# Schematic_Sensing_Module.net
KiCad netlist of a schematic drawn in EAGLE
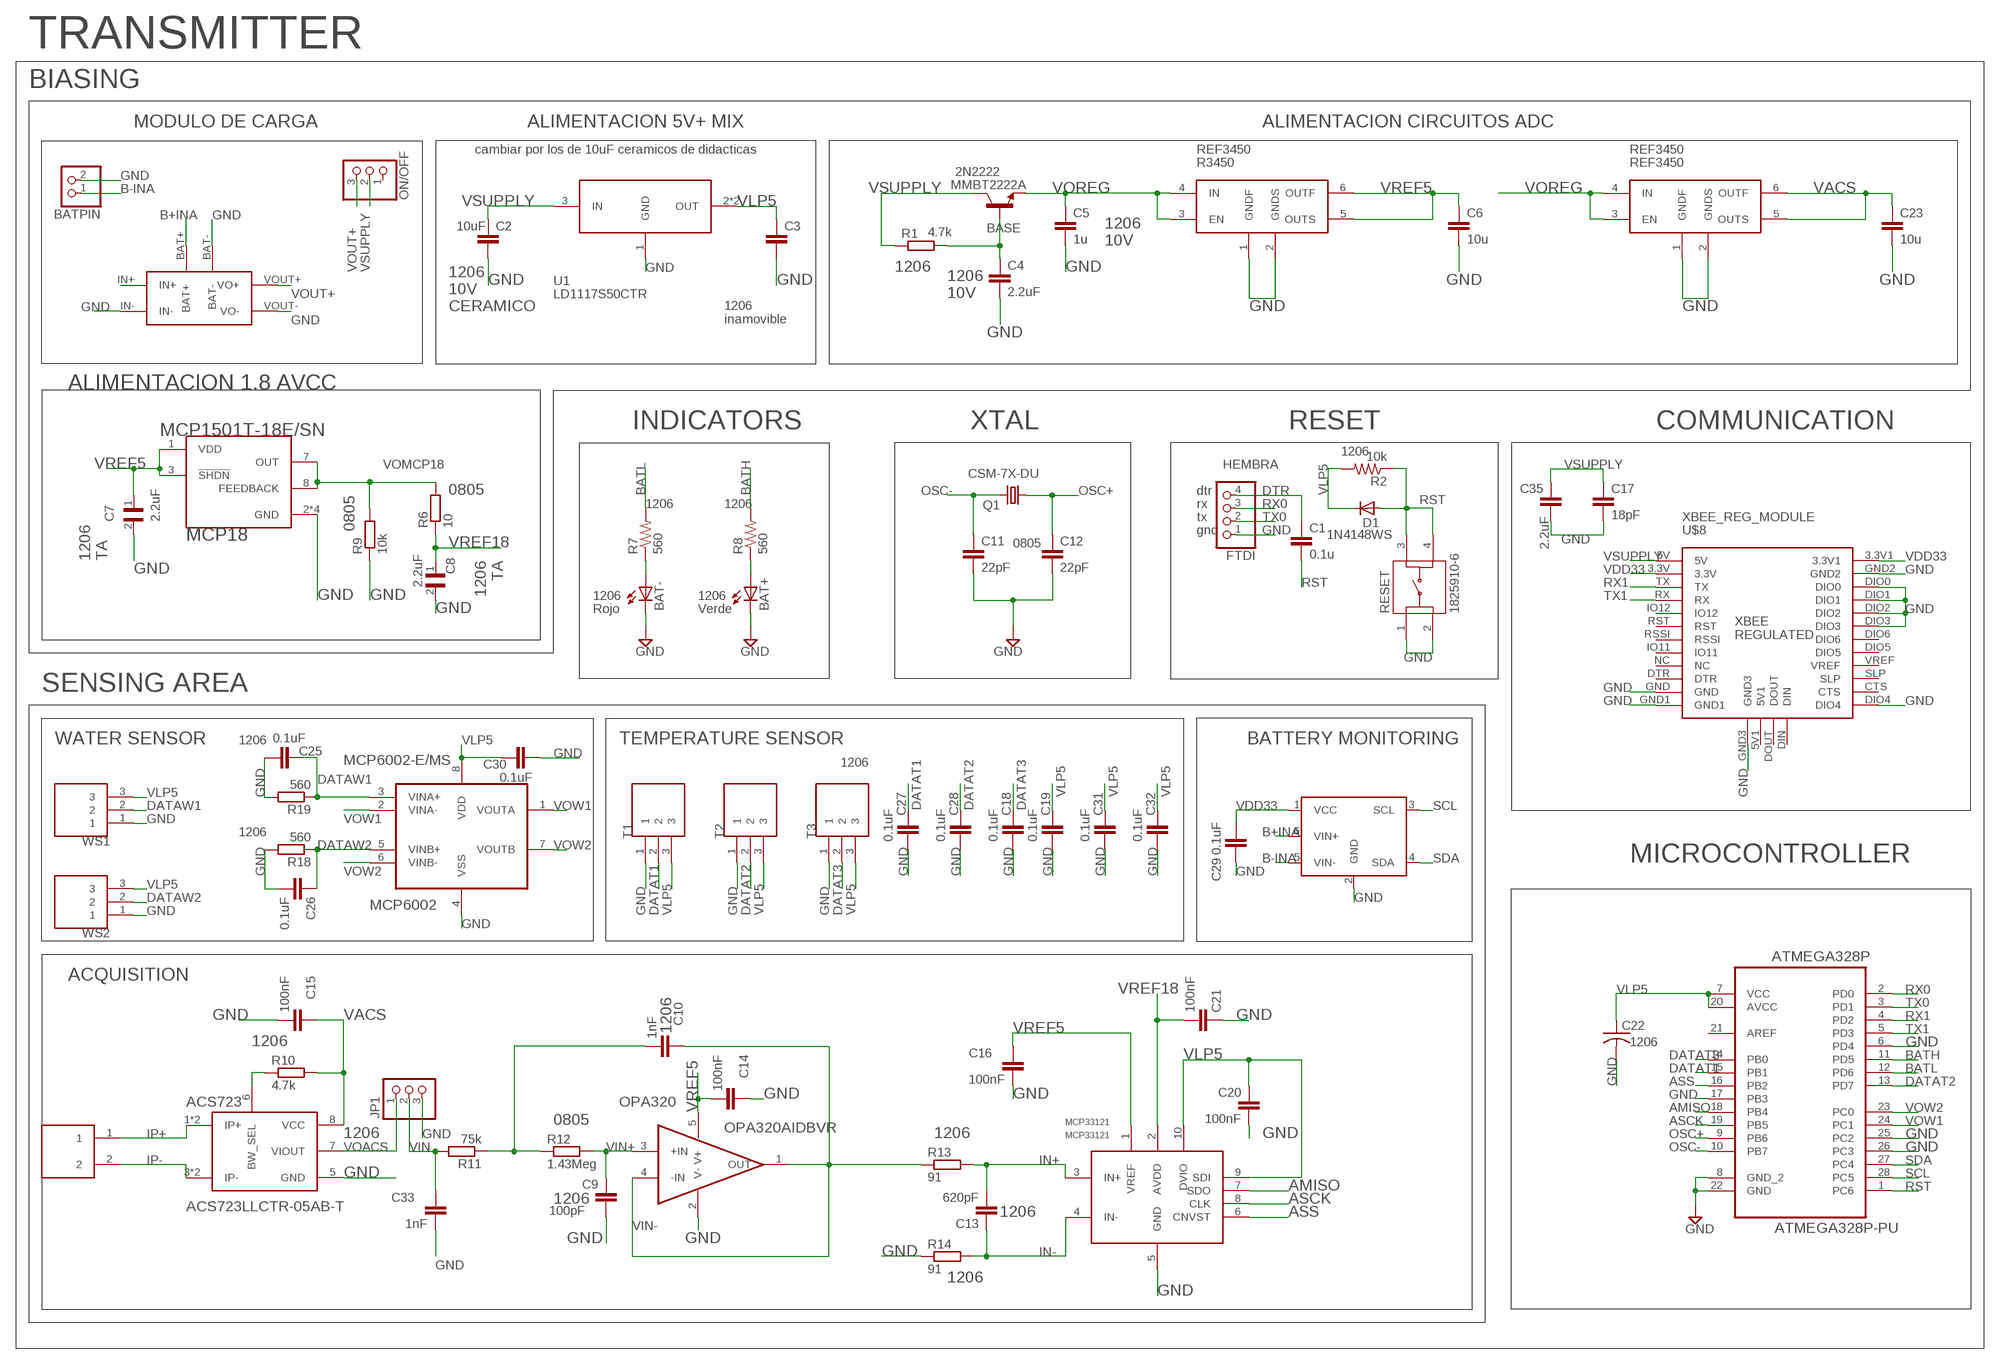
[diagram p0: schematic, sheet 1]

(export (version "E")
  (design (tool "Eeschema 10.0.6"))
  (components
    (comp (ref "2N2222")
      (value "MMBT2222A")
      (footprint "eagle-import:SOT23")
      (fields (field (name "MF") "ON Semiconductor"))
      (libsource (lib "eagle-import") (part "MMBT2222A"))
    )
    (comp (ref "ACS723")
      (value "ACS723LLCTR-05AB-T")
      (footprint "eagle-import:SOIC127P600X175-8N")
      (fields (field (name "MF") "ALPS"))
      (libsource (lib "eagle-import") (part "ACS723LLCTR-05AB-T"))
    )
    (comp (ref "ATMEGA328P")
      (value "ATMEGA328P-PU")
      (footprint "eagle-import:DIP254P762X457-28")
      (libsource (lib "eagle-import") (part "ATMEGA328P-PU"))
    )
    (comp (ref "BAT+")
      (value "LEDCHIPLED_1206")
      (footprint "eagle-import:CHIPLED_1206")
      (libsource (lib "eagle-import") (part "LEDCHIPLED_1206"))
    )
    (comp (ref "BAT-")
      (value "LEDCHIPLED_1206")
      (footprint "eagle-import:CHIPLED_1206")
      (libsource (lib "eagle-import") (part "LEDCHIPLED_1206"))
    )
    (comp (ref "BATPIN")
      (value "PINHD-1X2")
      (footprint "eagle-import:1X02")
      (libsource (lib "eagle-import") (part "PINHD-1X2"))
    )
    (comp (ref "C1")
      (value "0.1u")
      (footprint "eagle-import:C0805")
      (libsource (lib "eagle-import") (part "C-EUC0805"))
    )
    (comp (ref "C2")
      (value "10uF")
      (footprint "eagle-import:C1206")
      (libsource (lib "eagle-import") (part "rcl_334_C-EUC1206"))
    )
    (comp (ref "C3")
      (value "10uF")
      (footprint "eagle-import:C1206")
      (libsource (lib "eagle-import") (part "rcl_334_C-EUC1206"))
    )
    (comp (ref "C4")
      (value "2.2uF")
      (footprint "eagle-import:C1206")
      (libsource (lib "eagle-import") (part "rcl_334_C-EUC1206"))
    )
    (comp (ref "C5")
      (value "1u")
      (footprint "eagle-import:C1206")
      (libsource (lib "eagle-import") (part "rcl_334_C-EUC1206"))
    )
    (comp (ref "C6")
      (value "10u")
      (footprint "eagle-import:C1206")
      (libsource (lib "eagle-import") (part "rcl_334_C-EUC1206"))
    )
    (comp (ref "C7")
      (value "2.2uF")
      (footprint "eagle-import:CAPC3216X110N")
      (fields
        (field (name "DIGI-KEY_PART_NUMBER") "399-8268-2-ND")
        (field (name "MF") "KEMET")
        (field (name "MP") "T491A106K010AT7280")
      )
      (libsource (lib "eagle-import") (part "T491A106K010AT7280"))
    )
    (comp (ref "C8")
      (value "2.2uF")
      (footprint "eagle-import:CAPC3216X110N")
      (fields
        (field (name "DIGI-KEY_PART_NUMBER") "399-8268-2-ND")
        (field (name "MF") "KEMET")
        (field (name "MP") "T491A106K010AT7280")
      )
      (libsource (lib "eagle-import") (part "T491A106K010AT7280"))
    )
    (comp (ref "C9")
      (value "100pF")
      (footprint "eagle-import:C1206")
      (libsource (lib "eagle-import") (part "rcl_334_C-EUC1206"))
    )
    (comp (ref "C10")
      (value "1nF")
      (footprint "eagle-import:C1206")
      (libsource (lib "eagle-import") (part "rcl_334_C-EUC1206"))
    )
    (comp (ref "C11")
      (value "22pF")
      (footprint "eagle-import:C0805")
      (libsource (lib "eagle-import") (part "rcl_334_C-EUC0805"))
    )
    (comp (ref "C12")
      (value "22pF")
      (footprint "eagle-import:C0805")
      (libsource (lib "eagle-import") (part "rcl_334_C-EUC0805"))
    )
    (comp (ref "C13")
      (value "620pF")
      (footprint "eagle-import:C1206")
      (libsource (lib "eagle-import") (part "rcl_334_C-EUC1206"))
    )
    (comp (ref "C14")
      (value "100nF")
      (footprint "eagle-import:C1206")
      (libsource (lib "eagle-import") (part "rcl_334_C-EUC1206"))
    )
    (comp (ref "C15")
      (value "100nF")
      (footprint "eagle-import:C1206")
      (libsource (lib "eagle-import") (part "rcl_334_C-EUC1206"))
    )
    (comp (ref "C16")
      (value "100nF")
      (footprint "eagle-import:C1206")
      (libsource (lib "eagle-import") (part "rcl_334_C-EUC1206"))
    )
    (comp (ref "C17")
      (value "18pF")
      (footprint "eagle-import:C0805")
      (libsource (lib "eagle-import") (part "C-EUC0805"))
    )
    (comp (ref "C18")
      (value "0.1uF")
      (footprint "eagle-import:C1206")
      (libsource (lib "eagle-import") (part "rcl_334_C-EUC1206"))
    )
    (comp (ref "C19")
      (value "0.1uF")
      (footprint "eagle-import:C1206")
      (libsource (lib "eagle-import") (part "rcl_334_C-EUC1206"))
    )
    (comp (ref "C20")
      (value "100nF")
      (footprint "eagle-import:C1206")
      (libsource (lib "eagle-import") (part "rcl_334_C-EUC1206"))
    )
    (comp (ref "C21")
      (value "100nF")
      (footprint "eagle-import:C1206")
      (libsource (lib "eagle-import") (part "rcl_334_C-EUC1206"))
    )
    (comp (ref "C22")
      (value "0.1uF")
      (footprint "eagle-import:C1206")
      (libsource (lib "eagle-import") (part "C-USC1206"))
    )
    (comp (ref "C23")
      (value "10u")
      (footprint "eagle-import:C1206")
      (libsource (lib "eagle-import") (part "rcl_334_C-EUC1206"))
    )
    (comp (ref "C25")
      (value "0.1uF")
      (footprint "eagle-import:C1206")
      (libsource (lib "eagle-import") (part "rcl_334_C-EUC1206"))
    )
    (comp (ref "C26")
      (value "0.1uF")
      (footprint "eagle-import:C1206")
      (libsource (lib "eagle-import") (part "rcl_334_C-EUC1206"))
    )
    (comp (ref "C27")
      (value "0.1uF")
      (footprint "eagle-import:C1206")
      (libsource (lib "eagle-import") (part "rcl_334_C-EUC1206"))
    )
    (comp (ref "C28")
      (value "0.1uF")
      (footprint "eagle-import:C1206")
      (libsource (lib "eagle-import") (part "rcl_334_C-EUC1206"))
    )
    (comp (ref "C29")
      (value "0.1uF")
      (footprint "eagle-import:C1206")
      (libsource (lib "eagle-import") (part "rcl_334_C-EUC1206"))
    )
    (comp (ref "C30")
      (value "0.1uF")
      (footprint "eagle-import:C1206")
      (libsource (lib "eagle-import") (part "rcl_334_C-EUC1206"))
    )
    (comp (ref "C31")
      (value "0.1uF")
      (footprint "eagle-import:C1206")
      (libsource (lib "eagle-import") (part "rcl_334_C-EUC1206"))
    )
    (comp (ref "C32")
      (value "0.1uF")
      (footprint "eagle-import:C1206")
      (libsource (lib "eagle-import") (part "rcl_334_C-EUC1206"))
    )
    (comp (ref "C33")
      (value "1nF")
      (footprint "eagle-import:C1206")
      (libsource (lib "eagle-import") (part "rcl_334_C-EUC1206"))
    )
    (comp (ref "C35")
      (value "2.2uF")
      (footprint "eagle-import:C1206")
      (libsource (lib "eagle-import") (part "rcl_334_C-EUC1206"))
    )
    (comp (ref "D1")
      (value "1N4148WS")
      (footprint "eagle-import:SOD323")
      (fields (field (name "MF") "ON Semiconductor"))
      (libsource (lib "eagle-import") (part "1N4148WS"))
    )
    (comp (ref "FTDI")
      (value "PINHD-1X4")
      (footprint "eagle-import:1X04")
      (libsource (lib "eagle-import") (part "PINHD-1X4"))
    )
    (comp (ref "IACT")
      (value "TERMINAL-TB2")
      (footprint "eagle-import:TERMINAL-TB2")
      (libsource (lib "eagle-import") (part "TERMINAL-TB2"))
    )
    (comp (ref "INA219")
      (value "INABB")
      (footprint "eagle-import:INA219-MODULE")
      (libsource (lib "eagle-import") (part "INABB"))
    )
    (comp (ref "JP1")
      (value "PINHD-1X3")
      (footprint "eagle-import:1X03")
      (libsource (lib "eagle-import") (part "pinhead_325_PINHD-1X3"))
    )
    (comp (ref "MCP18")
      (value "MCP1501T-18E/SN")
      (footprint "eagle-import:SOIC127P600X175-8N")
      (fields (field (name "MF") "Microchip"))
      (libsource (lib "eagle-import") (part "MCP1501T-18E/SN"))
    )
    (comp (ref "MCP6002")
      (value "MCP6002-E/MS")
      (footprint "eagle-import:SOP65P490X110-8N")
      (fields (field (name "MF") "Microchip Technology"))
      (libsource (lib "eagle-import") (part "MCP6002-E/MS"))
    )
    (comp (ref "MCP33121")
      (value "MCP33121")
      (footprint "eagle-import:MSOP10")
      (libsource (lib "eagle-import") (part "MCP33121"))
    )
    (comp (ref "ON/OFF")
      (value "PINHD-1X3")
      (footprint "eagle-import:1X03")
      (libsource (lib "eagle-import") (part "PINHD-1X3"))
    )
    (comp (ref "OPA320")
      (value "OPA320AIDBVR")
      (footprint "eagle-import:SOT95P280X145-5N")
      (fields (field (name "DIGI-KEY_PART_NUMBER") "296-29480-1-ND") (field (name "MF") "Texas Instruments"))
      (libsource (lib "eagle-import") (part "OPA320AIDBVR"))
    )
    (comp (ref "POWER-SUPP")
      (value "MODULO_CARGA_DEVICE")
      (footprint "eagle-import:MODULO_CARGA")
      (libsource (lib "eagle-import") (part "MODULO_CARGA_DEVICE"))
    )
    (comp (ref "Q1")
      (value "CSM-7X-DU")
      (footprint "eagle-import:CSM-7X-DU")
      (libsource (lib "eagle-import") (part "CSM-7X-DU"))
    )
    (comp (ref "R1")
      (value "4.7k")
      (footprint "eagle-import:R1206")
      (libsource (lib "eagle-import") (part "R-EU_R1206"))
    )
    (comp (ref "R2")
      (value "10k")
      (footprint "eagle-import:R1206")
      (libsource (lib "eagle-import") (part "R-US_R1206"))
    )
    (comp (ref "R6")
      (value "10")
      (footprint "eagle-import:R0805")
      (libsource (lib "eagle-import") (part "R-EU_R0805"))
    )
    (comp (ref "R7")
      (value "560")
      (footprint "eagle-import:R1206")
      (libsource (lib "eagle-import") (part "R-US_R1206"))
    )
    (comp (ref "R8")
      (value "560")
      (footprint "eagle-import:R1206")
      (libsource (lib "eagle-import") (part "R-US_R1206"))
    )
    (comp (ref "R9")
      (value "10k")
      (footprint "eagle-import:R0805")
      (libsource (lib "eagle-import") (part "R-EU_R0805"))
    )
    (comp (ref "R10")
      (value "4.7k")
      (footprint "eagle-import:M1206")
      (libsource (lib "eagle-import") (part "R-EU_M1206"))
    )
    (comp (ref "R11")
      (value "75k")
      (footprint "eagle-import:R1206")
      (libsource (lib "eagle-import") (part "R-EU_R1206"))
    )
    (comp (ref "R12")
      (value "1.43Meg")
      (footprint "eagle-import:R0805")
      (libsource (lib "eagle-import") (part "R-EU_R0805"))
    )
    (comp (ref "R13")
      (value "91")
      (footprint "eagle-import:R1206")
      (libsource (lib "eagle-import") (part "R-EU_R1206"))
    )
    (comp (ref "R14")
      (value "91")
      (footprint "eagle-import:R1206")
      (libsource (lib "eagle-import") (part "R-EU_R1206"))
    )
    (comp (ref "R18")
      (value "560")
      (footprint "eagle-import:R1206")
      (libsource (lib "eagle-import") (part "R-EU_R1206"))
    )
    (comp (ref "R19")
      (value "560")
      (footprint "eagle-import:R1206")
      (libsource (lib "eagle-import") (part "R-EU_R1206"))
    )
    (comp (ref "R3450")
      (value "REF3450")
      (footprint "eagle-import:SOT95P280X145-6N")
      (libsource (lib "eagle-import") (part "REF3450"))
    )
    (comp (ref "REF3450")
      (value "REF3450")
      (footprint "eagle-import:SOT95P280X145-6N")
      (libsource (lib "eagle-import") (part "REF3450"))
    )
    (comp (ref "RESET")
      (value "1825910-6")
      (footprint "eagle-import:SW_1825910-6-4")
      (fields (field (name "MF") "TE Connectivity"))
      (libsource (lib "eagle-import") (part "1825910-6"))
    )
    (comp (ref "T1")
      (value "TERMINAL-TB3")
      (footprint "eagle-import:TERMINAL-TB3")
      (fields (field (name "MF") "CUI Devices") (field (name "MP") "TB001-500-03BE"))
      (libsource (lib "eagle-import") (part "TERMINAL-TB3"))
    )
    (comp (ref "T2")
      (value "TERMINAL-TB3")
      (footprint "eagle-import:TERMINAL-TB3")
      (fields (field (name "MF") "CUI Devices") (field (name "MP") "TB001-500-03BE"))
      (libsource (lib "eagle-import") (part "TERMINAL-TB3"))
    )
    (comp (ref "T3")
      (value "TERMINAL-TB3")
      (footprint "eagle-import:TERMINAL-TB3")
      (fields (field (name "MF") "CUI Devices") (field (name "MP") "TB001-500-03BE"))
      (libsource (lib "eagle-import") (part "TERMINAL-TB3"))
    )
    (comp (ref "U$8")
      (value "XBEE_REG_MODULE")
      (footprint "eagle-import:XBEE_REG")
      (libsource (lib "eagle-import") (part "XBEE_REG_MODULE"))
    )
    (comp (ref "U1")
      (value "LD1117S50CTR")
      (footprint "eagle-import:SOT223")
      (fields (field (name "MF") "STMicroelectronics"))
      (libsource (lib "eagle-import") (part "LD1117S50CTR"))
    )
    (comp (ref "WS1")
      (value "TERMINAL-TB3")
      (footprint "eagle-import:TERMINAL-TB3")
      (fields (field (name "MF") "CUI Devices") (field (name "MP") "TB001-500-03BE"))
      (libsource (lib "eagle-import") (part "TERMINAL-TB3"))
    )
    (comp (ref "WS2")
      (value "TERMINAL-TB3")
      (footprint "eagle-import:TERMINAL-TB3")
      (fields (field (name "MF") "CUI Devices") (field (name "MP") "TB001-500-03BE"))
      (libsource (lib "eagle-import") (part "TERMINAL-TB3"))
    )
  )
  (nets
    (net (code "1") (name "/AMISO") (class "Default")
      (node (ref "ATMEGA328P") (pin "18") (pinfunction "PB4_18") (pintype "bidirectional"))
      (node (ref "MCP33121") (pin "7") (pinfunction "SDO_7") (pintype "bidirectional"))
    )
    (net (code "2") (name "/ASCK") (class "Default")
      (node (ref "ATMEGA328P") (pin "19") (pinfunction "PB5_19") (pintype "bidirectional"))
      (node (ref "MCP33121") (pin "8") (pinfunction "CLK_8") (pintype "bidirectional"))
    )
    (net (code "3") (name "/ASS") (class "Default")
      (node (ref "ATMEGA328P") (pin "16") (pinfunction "PB2_16") (pintype "bidirectional"))
      (node (ref "MCP33121") (pin "6") (pinfunction "CNVST_6") (pintype "bidirectional"))
    )
    (net (code "4") (name "/B+INA") (class "Default")
      (node (ref "INA219") (pin "6") (pinfunction "VIN+_6") (pintype "bidirectional"))
      (node (ref "POWER-SUPP") (pin "BAT+") (pinfunction "BAT+_BAT+") (pintype "bidirectional"))
    )
    (net (code "5") (name "/B-INA") (class "Default")
      (node (ref "BATPIN") (pin "1") (pinfunction "1_1") (pintype "passive"))
      (node (ref "INA219") (pin "5") (pinfunction "VIN-_5") (pintype "bidirectional"))
    )
    (net (code "6") (name "/BASE") (class "Default")
      (node (ref "2N2222") (pin "1") (pinfunction "B_1") (pintype "passive"))
      (node (ref "C4") (pin "1") (pinfunction "1_1") (pintype "passive"))
      (node (ref "R1") (pin "2") (pinfunction "2_2") (pintype "passive"))
    )
    (net (code "7") (name "/BATH") (class "Default")
      (node (ref "ATMEGA328P") (pin "11") (pinfunction "PD5_11") (pintype "bidirectional"))
      (node (ref "R8") (pin "2") (pinfunction "2_2") (pintype "passive"))
    )
    (net (code "8") (name "/BATL") (class "Default")
      (node (ref "ATMEGA328P") (pin "12") (pinfunction "PD6_12") (pintype "bidirectional"))
      (node (ref "R7") (pin "2") (pinfunction "2_2") (pintype "passive"))
    )
    (net (code "9") (name "/DATAT1") (class "Default")
      (node (ref "ATMEGA328P") (pin "15") (pinfunction "PB1_15") (pintype "bidirectional"))
      (node (ref "C27") (pin "1") (pinfunction "1_1") (pintype "passive"))
      (node (ref "T1") (pin "2") (pinfunction "2_2") (pintype "passive"))
    )
    (net (code "10") (name "/DATAT2") (class "Default")
      (node (ref "ATMEGA328P") (pin "13") (pinfunction "PD7_13") (pintype "bidirectional"))
      (node (ref "C28") (pin "1") (pinfunction "1_1") (pintype "passive"))
      (node (ref "T2") (pin "2") (pinfunction "2_2") (pintype "passive"))
    )
    (net (code "11") (name "/DATAT3") (class "Default")
      (node (ref "ATMEGA328P") (pin "14") (pinfunction "PB0_14") (pintype "bidirectional"))
      (node (ref "C18") (pin "1") (pinfunction "1_1") (pintype "passive"))
      (node (ref "T3") (pin "2") (pinfunction "2_2") (pintype "passive"))
    )
    (net (code "12") (name "/DATAW1") (class "Default")
      (node (ref "C25") (pin "1") (pinfunction "1_1") (pintype "passive"))
      (node (ref "MCP6002") (pin "3") (pinfunction "VINA+_3") (pintype "input"))
      (node (ref "R19") (pin "1") (pinfunction "1_1") (pintype "passive"))
      (node (ref "WS1") (pin "2") (pinfunction "2_2") (pintype "passive"))
    )
    (net (code "13") (name "/DATAW2") (class "Default")
      (node (ref "C26") (pin "1") (pinfunction "1_1") (pintype "passive"))
      (node (ref "MCP6002") (pin "5") (pinfunction "VINB+_5") (pintype "input"))
      (node (ref "R18") (pin "1") (pinfunction "1_1") (pintype "passive"))
      (node (ref "WS2") (pin "2") (pinfunction "2_2") (pintype "passive"))
    )
    (net (code "14") (name "/DTR") (class "Default")
      (node (ref "C1") (pin "1") (pinfunction "1_1") (pintype "passive"))
      (node (ref "FTDI") (pin "4") (pinfunction "4_4") (pintype "passive"))
    )
    (net (code "15") (name "/IN+") (class "Default")
      (node (ref "C13") (pin "2") (pinfunction "2_2") (pintype "passive"))
      (node (ref "MCP33121") (pin "3") (pinfunction "IN+_3") (pintype "bidirectional"))
      (node (ref "R13") (pin "2") (pinfunction "2_2") (pintype "passive"))
    )
    (net (code "16") (name "/IN-") (class "Default")
      (node (ref "C13") (pin "1") (pinfunction "1_1") (pintype "passive"))
      (node (ref "MCP33121") (pin "4") (pinfunction "IN-_4") (pintype "bidirectional"))
      (node (ref "R14") (pin "2") (pinfunction "2_2") (pintype "passive"))
    )
    (net (code "17") (name "/IP+") (class "Default")
      (node (ref "ACS723") (pin "1") (pinfunction "IP+_1") (pintype "passive"))
      (node (ref "ACS723") (pin "2") (pinfunction "IP+_2") (pintype "passive"))
      (node (ref "IACT") (pin "1") (pinfunction "1_1") (pintype "bidirectional"))
    )
    (net (code "18") (name "/IP-") (class "Default")
      (node (ref "ACS723") (pin "3") (pinfunction "IP-_3") (pintype "passive"))
      (node (ref "ACS723") (pin "4") (pinfunction "IP-_4") (pintype "passive"))
      (node (ref "IACT") (pin "2") (pinfunction "2_2") (pintype "bidirectional"))
    )
    (net (code "19") (name "/OSC+") (class "Default")
      (node (ref "ATMEGA328P") (pin "9") (pinfunction "PB6_9") (pintype "bidirectional"))
      (node (ref "C12") (pin "1") (pinfunction "1_1") (pintype "passive"))
      (node (ref "Q1") (pin "1") (pinfunction "1_1") (pintype "passive"))
    )
    (net (code "20") (name "/OSC-") (class "Default")
      (node (ref "ATMEGA328P") (pin "10") (pinfunction "PB7_10") (pintype "bidirectional"))
      (node (ref "C11") (pin "1") (pinfunction "1_1") (pintype "passive"))
      (node (ref "Q1") (pin "2") (pinfunction "2_2") (pintype "passive"))
    )
    (net (code "21") (name "/RST") (class "Default")
      (node (ref "ATMEGA328P") (pin "1") (pinfunction "PC6_1") (pintype "bidirectional"))
      (node (ref "C1") (pin "2") (pinfunction "2_2") (pintype "passive"))
      (node (ref "D1") (pin "A") (pinfunction "A_A") (pintype "passive"))
      (node (ref "R2") (pin "1") (pinfunction "1_1") (pintype "passive"))
      (node (ref "RESET") (pin "3") (pinfunction "3_3") (pintype "passive"))
      (node (ref "RESET") (pin "4") (pinfunction "4_4") (pintype "passive"))
    )
    (net (code "22") (name "/RX0") (class "Default")
      (node (ref "ATMEGA328P") (pin "2") (pinfunction "PD0_2") (pintype "bidirectional"))
      (node (ref "FTDI") (pin "3") (pinfunction "3_3") (pintype "passive"))
    )
    (net (code "23") (name "/RX1") (class "Default")
      (node (ref "ATMEGA328P") (pin "4") (pinfunction "PD2_4") (pintype "bidirectional"))
      (node (ref "U$8") (pin "TX") (pinfunction "TX_TX") (pintype "bidirectional"))
    )
    (net (code "24") (name "/SCL") (class "Default")
      (node (ref "ATMEGA328P") (pin "28") (pinfunction "PC5_28") (pintype "bidirectional"))
      (node (ref "INA219") (pin "3") (pinfunction "SCL_3") (pintype "bidirectional"))
    )
    (net (code "25") (name "/SDA") (class "Default")
      (node (ref "ATMEGA328P") (pin "27") (pinfunction "PC4_27") (pintype "bidirectional"))
      (node (ref "INA219") (pin "4") (pinfunction "SDA_4") (pintype "bidirectional"))
    )
    (net (code "26") (name "/TX0") (class "Default")
      (node (ref "ATMEGA328P") (pin "3") (pinfunction "PD1_3") (pintype "bidirectional"))
      (node (ref "FTDI") (pin "2") (pinfunction "2_2") (pintype "passive"))
    )
    (net (code "27") (name "/TX1") (class "Default")
      (node (ref "ATMEGA328P") (pin "5") (pinfunction "PD3_5") (pintype "bidirectional"))
      (node (ref "U$8") (pin "RX") (pinfunction "RX_RX") (pintype "bidirectional"))
    )
    (net (code "28") (name "/VACS") (class "Default")
      (node (ref "ACS723") (pin "8") (pinfunction "VCC_8") (pintype "power_in"))
      (node (ref "C15") (pin "1") (pinfunction "1_1") (pintype "passive"))
      (node (ref "C23") (pin "1") (pinfunction "1_1") (pintype "passive"))
      (node (ref "R10") (pin "2") (pinfunction "2_2") (pintype "passive"))
      (node (ref "REF3450") (pin "5") (pinfunction "OUTS_5") (pintype "bidirectional"))
      (node (ref "REF3450") (pin "6") (pinfunction "OUTF_6") (pintype "bidirectional"))
    )
    (net (code "29") (name "/VDD33") (class "Default")
      (node (ref "C29") (pin "1") (pinfunction "1_1") (pintype "passive"))
      (node (ref "INA219") (pin "1") (pinfunction "VCC_1") (pintype "bidirectional"))
      (node (ref "U$8") (pin "3.3V") (pinfunction "3.3V_3.3V") (pintype "bidirectional"))
      (node (ref "U$8") (pin "3.3V1") (pinfunction "3.3V1_3.3V1") (pintype "bidirectional"))
    )
    (net (code "30") (name "/VIN") (class "Default")
      (node (ref "C33") (pin "1") (pinfunction "1_1") (pintype "passive"))
      (node (ref "JP1") (pin "2") (pinfunction "2_2") (pintype "passive"))
      (node (ref "R11") (pin "2") (pinfunction "2_2") (pintype "passive"))
    )
    (net (code "31") (name "/VIN+") (class "Default")
      (node (ref "C9") (pin "1") (pinfunction "1_1") (pintype "passive"))
      (node (ref "OPA320") (pin "3") (pinfunction "+IN_3") (pintype "input"))
      (node (ref "R12") (pin "2") (pinfunction "2_2") (pintype "passive"))
    )
    (net (code "32") (name "/VIN-") (class "Default")
      (node (ref "C10") (pin "1") (pinfunction "1_1") (pintype "passive"))
      (node (ref "OPA320") (pin "1") (pinfunction "OUT_1") (pintype "output"))
      (node (ref "OPA320") (pin "4") (pinfunction "-IN_4") (pintype "input"))
      (node (ref "R13") (pin "1") (pinfunction "1_1") (pintype "passive"))
    )
    (net (code "33") (name "/VLP5") (class "Default")
      (node (ref "ATMEGA328P") (pin "20") (pinfunction "AVCC_20") (pintype "power_in"))
      (node (ref "ATMEGA328P") (pin "7") (pinfunction "VCC_7") (pintype "power_in"))
      (node (ref "C19") (pin "1") (pinfunction "1_1") (pintype "passive"))
      (node (ref "C20") (pin "1") (pinfunction "1_1") (pintype "passive"))
      (node (ref "C22") (pin "1") (pinfunction "1_1") (pintype "passive"))
      (node (ref "C3") (pin "1") (pinfunction "1_1") (pintype "passive"))
      (node (ref "C30") (pin "1") (pinfunction "1_1") (pintype "passive"))
      (node (ref "C31") (pin "1") (pinfunction "1_1") (pintype "passive"))
      (node (ref "C32") (pin "1") (pinfunction "1_1") (pintype "passive"))
      (node (ref "D1") (pin "C") (pinfunction "C_C") (pintype "passive"))
      (node (ref "MCP33121") (pin "10") (pinfunction "DVIO_10") (pintype "bidirectional"))
      (node (ref "MCP33121") (pin "9") (pinfunction "SDI_9") (pintype "bidirectional"))
      (node (ref "MCP6002") (pin "8") (pinfunction "VDD_8") (pintype "power_in"))
      (node (ref "R2") (pin "2") (pinfunction "2_2") (pintype "passive"))
      (node (ref "T1") (pin "3") (pinfunction "3_3") (pintype "passive"))
      (node (ref "T2") (pin "3") (pinfunction "3_3") (pintype "passive"))
      (node (ref "T3") (pin "3") (pinfunction "3_3") (pintype "passive"))
      (node (ref "U1") (pin "2") (pinfunction "OUT_2") (pintype "output"))
      (node (ref "U1") (pin "4") (pinfunction "OUT_4") (pintype "output"))
      (node (ref "WS1") (pin "3") (pinfunction "3_3") (pintype "passive"))
      (node (ref "WS2") (pin "3") (pinfunction "3_3") (pintype "passive"))
    )
    (net (code "34") (name "/VOACS") (class "Default")
      (node (ref "ACS723") (pin "7") (pinfunction "VIOUT_7") (pintype "output"))
      (node (ref "JP1") (pin "1") (pinfunction "1_1") (pintype "passive"))
    )
    (net (code "35") (name "/VOMCP18") (class "Default")
      (node (ref "MCP18") (pin "7") (pinfunction "OUT_7") (pintype "output"))
      (node (ref "MCP18") (pin "8") (pinfunction "FEEDBACK_8") (pintype "passive"))
      (node (ref "R6") (pin "2") (pinfunction "2_2") (pintype "passive"))
      (node (ref "R9") (pin "2") (pinfunction "2_2") (pintype "passive"))
    )
    (net (code "36") (name "/VOREG") (class "Default")
      (node (ref "2N2222") (pin "2") (pinfunction "E_2") (pintype "passive"))
      (node (ref "C5") (pin "1") (pinfunction "1_1") (pintype "passive"))
      (node (ref "R3450") (pin "3") (pinfunction "EN_3") (pintype "bidirectional"))
      (node (ref "R3450") (pin "4") (pinfunction "IN_4") (pintype "bidirectional"))
      (node (ref "REF3450") (pin "3") (pinfunction "EN_3") (pintype "bidirectional"))
      (node (ref "REF3450") (pin "4") (pinfunction "IN_4") (pintype "bidirectional"))
    )
    (net (code "37") (name "/VOUT+") (class "Default")
      (node (ref "ON/OFF") (pin "3") (pinfunction "3_3") (pintype "passive"))
      (node (ref "POWER-SUPP") (pin "VOUT+") (pinfunction "VO+_VOUT+") (pintype "bidirectional"))
    )
    (net (code "38") (name "/VOW1") (class "Default")
      (node (ref "ATMEGA328P") (pin "24") (pinfunction "PC1_24") (pintype "bidirectional"))
      (node (ref "MCP6002") (pin "1") (pinfunction "VOUTA_1") (pintype "output"))
      (node (ref "MCP6002") (pin "2") (pinfunction "VINA-_2") (pintype "input"))
    )
    (net (code "39") (name "/VOW2") (class "Default")
      (node (ref "ATMEGA328P") (pin "23") (pinfunction "PC0_23") (pintype "bidirectional"))
      (node (ref "MCP6002") (pin "6") (pinfunction "VINB-_6") (pintype "input"))
      (node (ref "MCP6002") (pin "7") (pinfunction "VOUTB_7") (pintype "output"))
    )
    (net (code "40") (name "/VREF5") (class "Default")
      (node (ref "C14") (pin "2") (pinfunction "2_2") (pintype "passive"))
      (node (ref "C16") (pin "1") (pinfunction "1_1") (pintype "passive"))
      (node (ref "C6") (pin "1") (pinfunction "1_1") (pintype "passive"))
      (node (ref "C7") (pin "1") (pinfunction "1_1") (pintype "passive"))
      (node (ref "MCP18") (pin "1") (pinfunction "VDD_1") (pintype "power_in"))
      (node (ref "MCP18") (pin "3") (pinfunction "~{SHDN}_3") (pintype "input"))
      (node (ref "MCP33121") (pin "1") (pinfunction "VREF_1") (pintype "bidirectional"))
      (node (ref "OPA320") (pin "5") (pinfunction "V+_5") (pintype "power_in"))
      (node (ref "R3450") (pin "5") (pinfunction "OUTS_5") (pintype "bidirectional"))
      (node (ref "R3450") (pin "6") (pinfunction "OUTF_6") (pintype "bidirectional"))
    )
    (net (code "41") (name "/VREF18") (class "Default")
      (node (ref "C21") (pin "2") (pinfunction "2_2") (pintype "passive"))
      (node (ref "C8") (pin "1") (pinfunction "1_1") (pintype "passive"))
      (node (ref "MCP33121") (pin "2") (pinfunction "AVDD_2") (pintype "bidirectional"))
      (node (ref "R6") (pin "1") (pinfunction "1_1") (pintype "passive"))
    )
    (net (code "42") (name "/VSUPPLY") (class "Default")
      (node (ref "2N2222") (pin "3") (pinfunction "C_3") (pintype "passive"))
      (node (ref "C17") (pin "1") (pinfunction "1_1") (pintype "passive"))
      (node (ref "C2") (pin "1") (pinfunction "1_1") (pintype "passive"))
      (node (ref "C35") (pin "1") (pinfunction "1_1") (pintype "passive"))
      (node (ref "ON/OFF") (pin "2") (pinfunction "2_2") (pintype "passive"))
      (node (ref "R1") (pin "1") (pinfunction "1_1") (pintype "passive"))
      (node (ref "U$8") (pin "5V") (pinfunction "5V_5V") (pintype "bidirectional"))
      (node (ref "U1") (pin "3") (pinfunction "IN_3") (pintype "input"))
    )
    (net (code "43") (name "GND") (class "Default")
      (node (ref "ACS723") (pin "5") (pinfunction "GND_5") (pintype "power_in"))
      (node (ref "ATMEGA328P") (pin "17") (pinfunction "PB3_17") (pintype "bidirectional"))
      (node (ref "ATMEGA328P") (pin "22") (pinfunction "GND_22") (pintype "passive"))
      (node (ref "ATMEGA328P") (pin "25") (pinfunction "PC2_25") (pintype "bidirectional"))
      (node (ref "ATMEGA328P") (pin "26") (pinfunction "PC3_26") (pintype "bidirectional"))
      (node (ref "ATMEGA328P") (pin "6") (pinfunction "PD4_6") (pintype "bidirectional"))
      (node (ref "ATMEGA328P") (pin "8") (pinfunction "GND_2_8") (pintype "passive"))
      (node (ref "BAT+") (pin "C") (pinfunction "C_C") (pintype "passive"))
      (node (ref "BAT-") (pin "C") (pinfunction "C_C") (pintype "passive"))
      (node (ref "BATPIN") (pin "2") (pinfunction "2_2") (pintype "passive"))
      (node (ref "C11") (pin "2") (pinfunction "2_2") (pintype "passive"))
      (node (ref "C12") (pin "2") (pinfunction "2_2") (pintype "passive"))
      (node (ref "C14") (pin "1") (pinfunction "1_1") (pintype "passive"))
      (node (ref "C15") (pin "2") (pinfunction "2_2") (pintype "passive"))
      (node (ref "C16") (pin "2") (pinfunction "2_2") (pintype "passive"))
      (node (ref "C17") (pin "2") (pinfunction "2_2") (pintype "passive"))
      (node (ref "C18") (pin "2") (pinfunction "2_2") (pintype "passive"))
      (node (ref "C19") (pin "2") (pinfunction "2_2") (pintype "passive"))
      (node (ref "C2") (pin "2") (pinfunction "2_2") (pintype "passive"))
      (node (ref "C20") (pin "2") (pinfunction "2_2") (pintype "passive"))
      (node (ref "C21") (pin "1") (pinfunction "1_1") (pintype "passive"))
      (node (ref "C22") (pin "2") (pinfunction "2_2") (pintype "passive"))
      (node (ref "C23") (pin "2") (pinfunction "2_2") (pintype "passive"))
      (node (ref "C25") (pin "2") (pinfunction "2_2") (pintype "passive"))
      (node (ref "C26") (pin "2") (pinfunction "2_2") (pintype "passive"))
      (node (ref "C27") (pin "2") (pinfunction "2_2") (pintype "passive"))
      (node (ref "C28") (pin "2") (pinfunction "2_2") (pintype "passive"))
      (node (ref "C29") (pin "2") (pinfunction "2_2") (pintype "passive"))
      (node (ref "C3") (pin "2") (pinfunction "2_2") (pintype "passive"))
      (node (ref "C30") (pin "2") (pinfunction "2_2") (pintype "passive"))
      (node (ref "C31") (pin "2") (pinfunction "2_2") (pintype "passive"))
      (node (ref "C32") (pin "2") (pinfunction "2_2") (pintype "passive"))
      (node (ref "C33") (pin "2") (pinfunction "2_2") (pintype "passive"))
      (node (ref "C35") (pin "2") (pinfunction "2_2") (pintype "passive"))
      (node (ref "C4") (pin "2") (pinfunction "2_2") (pintype "passive"))
      (node (ref "C5") (pin "2") (pinfunction "2_2") (pintype "passive"))
      (node (ref "C6") (pin "2") (pinfunction "2_2") (pintype "passive"))
      (node (ref "C7") (pin "2") (pinfunction "2_2") (pintype "passive"))
      (node (ref "C8") (pin "2") (pinfunction "2_2") (pintype "passive"))
      (node (ref "C9") (pin "2") (pinfunction "2_2") (pintype "passive"))
      (node (ref "FTDI") (pin "1") (pinfunction "1_1") (pintype "passive"))
      (node (ref "INA219") (pin "2") (pinfunction "GND_2") (pintype "bidirectional"))
      (node (ref "JP1") (pin "3") (pinfunction "3_3") (pintype "passive"))
      (node (ref "MCP18") (pin "2") (pinfunction "GND_2") (pintype "passive"))
      (node (ref "MCP18") (pin "4") (pinfunction "GND_4") (pintype "passive"))
      (node (ref "MCP18") (pin "5") (pinfunction "GND_5") (pintype "passive"))
      (node (ref "MCP18") (pin "6") (pinfunction "GND_6") (pintype "passive"))
      (node (ref "MCP33121") (pin "5") (pinfunction "GND_5") (pintype "bidirectional"))
      (node (ref "MCP6002") (pin "4") (pinfunction "VSS_4") (pintype "power_in"))
      (node (ref "OPA320") (pin "2") (pinfunction "V-_2") (pintype "power_in"))
      (node (ref "POWER-SUPP") (pin "BAT-") (pinfunction "BAT-_BAT-") (pintype "bidirectional"))
      (node (ref "POWER-SUPP") (pin "IN-") (pinfunction "IN-_IN-") (pintype "bidirectional"))
      (node (ref "POWER-SUPP") (pin "VOUT-") (pinfunction "VO-_VOUT-") (pintype "bidirectional"))
      (node (ref "R14") (pin "1") (pinfunction "1_1") (pintype "passive"))
      (node (ref "R18") (pin "2") (pinfunction "2_2") (pintype "passive"))
      (node (ref "R19") (pin "2") (pinfunction "2_2") (pintype "passive"))
      (node (ref "R3450") (pin "1") (pinfunction "GNDF_1") (pintype "bidirectional"))
      (node (ref "R3450") (pin "2") (pinfunction "GNDS_2") (pintype "bidirectional"))
      (node (ref "R9") (pin "1") (pinfunction "1_1") (pintype "passive"))
      (node (ref "REF3450") (pin "1") (pinfunction "GNDF_1") (pintype "bidirectional"))
      (node (ref "REF3450") (pin "2") (pinfunction "GNDS_2") (pintype "bidirectional"))
      (node (ref "RESET") (pin "1") (pinfunction "1_1") (pintype "passive"))
      (node (ref "RESET") (pin "2") (pinfunction "2_2") (pintype "passive"))
      (node (ref "T1") (pin "1") (pinfunction "1_1") (pintype "passive"))
      (node (ref "T2") (pin "1") (pinfunction "1_1") (pintype "passive"))
      (node (ref "T3") (pin "1") (pinfunction "1_1") (pintype "passive"))
      (node (ref "U$8") (pin "DIO0") (pinfunction "DIO0_DIO0") (pintype "bidirectional"))
      (node (ref "U$8") (pin "DIO1") (pinfunction "DIO1_DIO1") (pintype "bidirectional"))
      (node (ref "U$8") (pin "DIO2") (pinfunction "DIO2_DIO2") (pintype "bidirectional"))
      (node (ref "U$8") (pin "DIO3") (pinfunction "DIO3_DIO3") (pintype "bidirectional"))
      (node (ref "U$8") (pin "DIO4") (pinfunction "DIO4_DIO4") (pintype "bidirectional"))
      (node (ref "U$8") (pin "GND") (pinfunction "GND_GND") (pintype "bidirectional"))
      (node (ref "U$8") (pin "GND1") (pinfunction "GND1_GND1") (pintype "bidirectional"))
      (node (ref "U$8") (pin "GND2") (pinfunction "GND2_GND2") (pintype "bidirectional"))
      (node (ref "U$8") (pin "GND3") (pinfunction "GND3_GND3") (pintype "bidirectional"))
      (node (ref "U1") (pin "1") (pinfunction "GND_1") (pintype "passive"))
      (node (ref "WS1") (pin "1") (pinfunction "1_1") (pintype "passive"))
      (node (ref "WS2") (pin "1") (pinfunction "1_1") (pintype "passive"))
    )
    (net (code "44") (name "Net-(ACS723-BW_SEL)") (class "Default")
      (node (ref "ACS723") (pin "6") (pinfunction "BW_SEL_6") (pintype "input"))
      (node (ref "R10") (pin "1") (pinfunction "1_1") (pintype "passive"))
    )
    (net (code "45") (name "Net-(BAT+-PadA)") (class "Default")
      (node (ref "BAT+") (pin "A") (pinfunction "A_A") (pintype "passive"))
      (node (ref "R8") (pin "1") (pinfunction "1_1") (pintype "passive"))
    )
    (net (code "46") (name "Net-(BAT--PadA)") (class "Default")
      (node (ref "BAT-") (pin "A") (pinfunction "A_A") (pintype "passive"))
      (node (ref "R7") (pin "1") (pinfunction "1_1") (pintype "passive"))
    )
    (net (code "47") (name "Net-(C10-Pad2)") (class "Default")
      (node (ref "C10") (pin "2") (pinfunction "2_2") (pintype "passive"))
      (node (ref "R11") (pin "1") (pinfunction "1_1") (pintype "passive"))
      (node (ref "R12") (pin "1") (pinfunction "1_1") (pintype "passive"))
    )
    (net (code "48") (name "unconnected-(ATMEGA328P-AREF-Pad21)") (class "Default")
      (node (ref "ATMEGA328P") (pin "21") (pinfunction "AREF_21") (pintype "input"))
    )
    (net (code "49") (name "unconnected-(ON/OFF-Pad1)") (class "Default")
      (node (ref "ON/OFF") (pin "1") (pinfunction "1_1") (pintype "passive"))
    )
    (net (code "50") (name "unconnected-(POWER-SUPP-PadIN+)") (class "Default")
      (node (ref "POWER-SUPP") (pin "IN+") (pinfunction "IN+_IN+") (pintype "bidirectional"))
    )
    (net (code "51") (name "unconnected-(U$8-Pad5V1)") (class "Default")
      (node (ref "U$8") (pin "5V1") (pinfunction "5V1_5V1") (pintype "bidirectional"))
    )
    (net (code "52") (name "unconnected-(U$8-PadCTS)") (class "Default")
      (node (ref "U$8") (pin "CTS") (pinfunction "CTS_CTS") (pintype "bidirectional"))
    )
    (net (code "53") (name "unconnected-(U$8-PadDIN)") (class "Default")
      (node (ref "U$8") (pin "DIN") (pinfunction "DIN_DIN") (pintype "bidirectional"))
    )
    (net (code "54") (name "unconnected-(U$8-PadDIO5)") (class "Default")
      (node (ref "U$8") (pin "DIO5") (pinfunction "DIO5_DIO5") (pintype "bidirectional"))
    )
    (net (code "55") (name "unconnected-(U$8-PadDIO6)") (class "Default")
      (node (ref "U$8") (pin "DIO6") (pinfunction "DIO6_DIO6") (pintype "bidirectional"))
    )
    (net (code "56") (name "unconnected-(U$8-PadDOUT)") (class "Default")
      (node (ref "U$8") (pin "DOUT") (pinfunction "DOUT_DOUT") (pintype "bidirectional"))
    )
    (net (code "57") (name "unconnected-(U$8-PadDTR)") (class "Default")
      (node (ref "U$8") (pin "DTR") (pinfunction "DTR_DTR") (pintype "bidirectional"))
    )
    (net (code "58") (name "unconnected-(U$8-PadIO11)") (class "Default")
      (node (ref "U$8") (pin "IO11") (pinfunction "IO11_IO11") (pintype "bidirectional"))
    )
    (net (code "59") (name "unconnected-(U$8-PadIO12)") (class "Default")
      (node (ref "U$8") (pin "IO12") (pinfunction "IO12_IO12") (pintype "bidirectional"))
    )
    (net (code "60") (name "unconnected-(U$8-PadNC)") (class "Default")
      (node (ref "U$8") (pin "NC") (pinfunction "NC_NC") (pintype "bidirectional"))
    )
    (net (code "61") (name "unconnected-(U$8-PadRSSI)") (class "Default")
      (node (ref "U$8") (pin "RSSI") (pinfunction "RSSI_RSSI") (pintype "bidirectional"))
    )
    (net (code "62") (name "unconnected-(U$8-PadRST)") (class "Default")
      (node (ref "U$8") (pin "RST") (pinfunction "RST_RST") (pintype "bidirectional"))
    )
    (net (code "63") (name "unconnected-(U$8-PadSLP)") (class "Default")
      (node (ref "U$8") (pin "SLP") (pinfunction "SLP_SLP") (pintype "bidirectional"))
    )
    (net (code "64") (name "unconnected-(U$8-PadVREF)") (class "Default")
      (node (ref "U$8") (pin "VREF") (pinfunction "VREF_VREF") (pintype "bidirectional"))
    )
  )
)
